# EquisatSimulatorV2.net
KiCad netlist of a schematic drawn in EAGLE
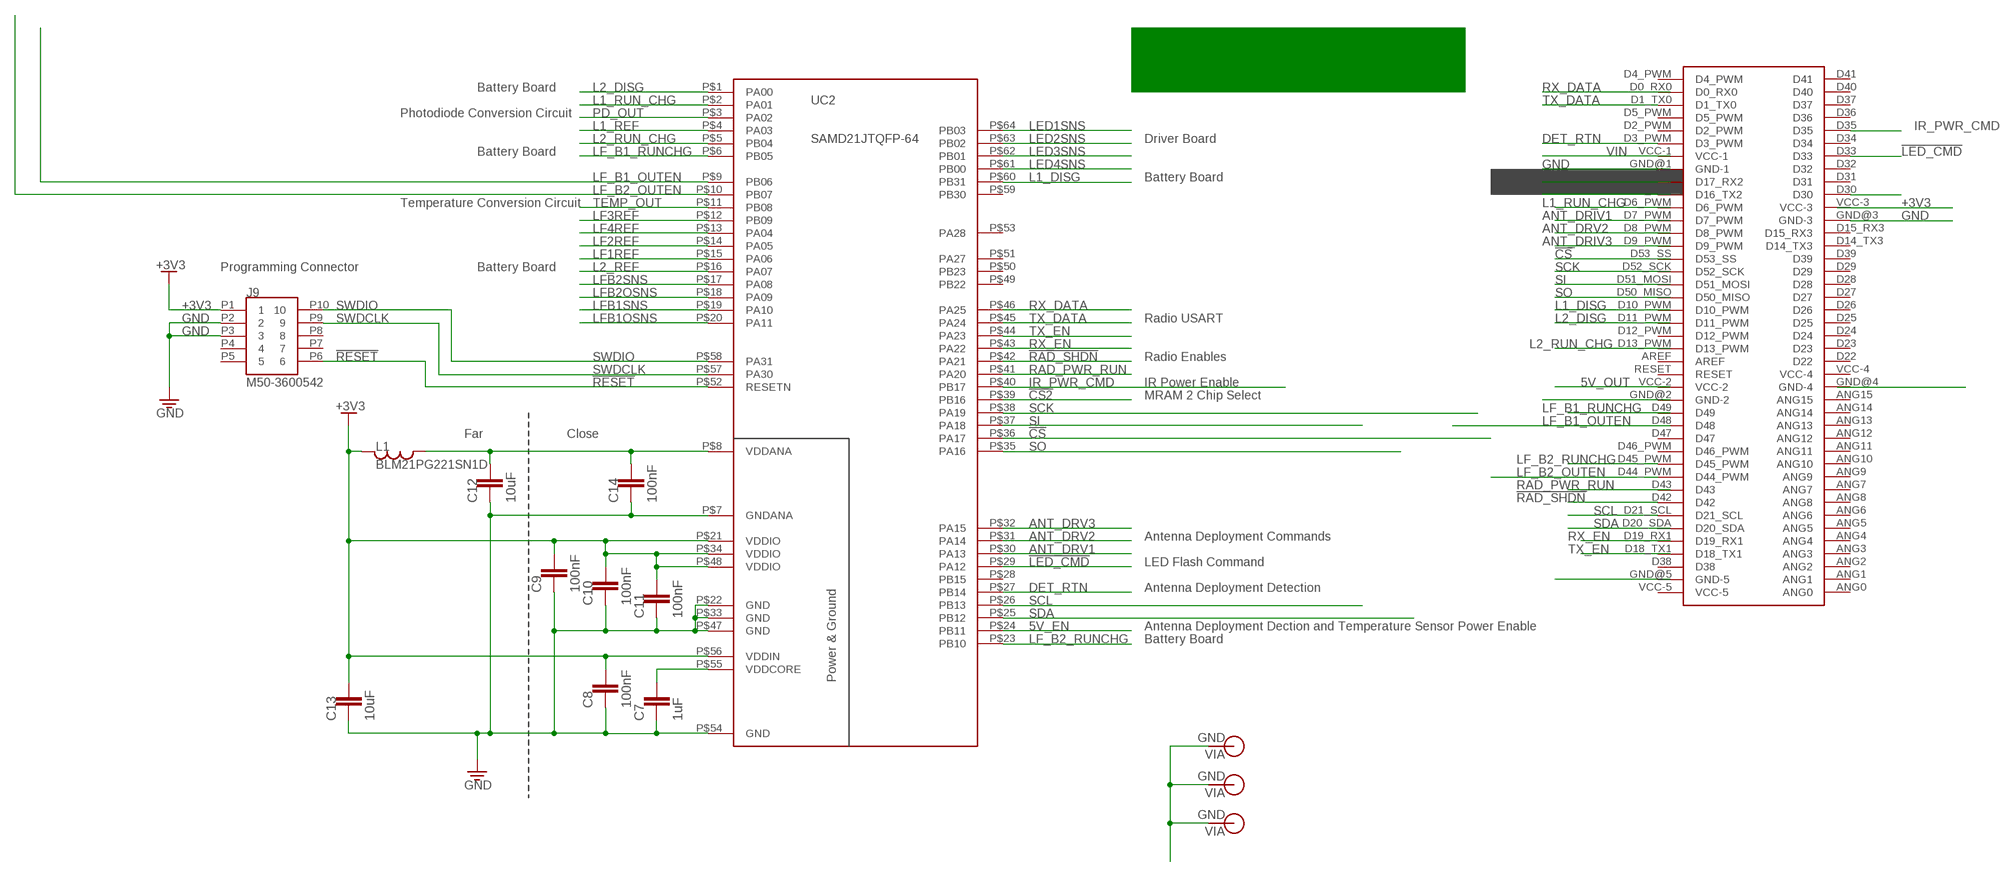
[diagram p0: schematic, sheet 1]

(export (version "E")
  (design (tool "Eeschema 10.0.6"))
  (components
    (comp (ref "C7")
      (value "1uF")
      (footprint "eagle-import:0805")
      (libsource (lib "eagle-import") (part "CAP0805"))
    )
    (comp (ref "C8")
      (value "100nF")
      (footprint "eagle-import:0805")
      (libsource (lib "eagle-import") (part "CAP0805"))
    )
    (comp (ref "C9")
      (value "100nF")
      (footprint "eagle-import:0805")
      (libsource (lib "eagle-import") (part "CAP0805"))
    )
    (comp (ref "C10")
      (value "100nF")
      (footprint "eagle-import:0805")
      (libsource (lib "eagle-import") (part "CAP0805"))
    )
    (comp (ref "C11")
      (value "100nF")
      (footprint "eagle-import:0805")
      (libsource (lib "eagle-import") (part "CAP0805"))
    )
    (comp (ref "C12")
      (value "10uF")
      (footprint "eagle-import:0805")
      (libsource (lib "eagle-import") (part "CAP0805"))
    )
    (comp (ref "C13")
      (value "10uF")
      (footprint "eagle-import:0805")
      (libsource (lib "eagle-import") (part "CAP0805"))
    )
    (comp (ref "C14")
      (value "100nF")
      (footprint "eagle-import:0805")
      (libsource (lib "eagle-import") (part "CAP0805"))
    )
    (comp (ref "J9")
      (value "M50-3600542")
      (footprint "eagle-import:10PINMALE")
      (libsource (lib "eagle-import") (part "10PINMALE"))
    )
    (comp (ref "L1")
      (value "BLM21PG221SN1D")
      (footprint "eagle-import:0805")
      (libsource (lib "eagle-import") (part "FERRITE"))
    )
    (comp (ref "U$1")
      (value "ARDUINOMEGABOARD")
      (footprint "eagle-import:ARDUINOMEGA")
      (libsource (lib "eagle-import") (part "ARDUINOMEGABOARD"))
    )
    (comp (ref "UC2")
      (value "SAMD21JTQFP-64")
      (footprint "eagle-import:TQFP-64")
      (libsource (lib "eagle-import") (part "SAMD21JTQFP-64"))
    )
    (comp (ref "V9")
      (value "GND")
      (footprint "eagle-import:VIA-60MIL-SQ")
      (libsource (lib "eagle-import") (part "VIA60MIL-SQ"))
    )
    (comp (ref "V10")
      (value "GND")
      (footprint "eagle-import:VIA-60MIL-SQ")
      (libsource (lib "eagle-import") (part "VIA60MIL-SQ"))
    )
    (comp (ref "V12")
      (value "GND")
      (footprint "eagle-import:VIA-60MIL-SQ")
      (libsource (lib "eagle-import") (part "VIA60MIL-SQ"))
    )
  )
  (nets
    (net (code "1") (name "+3V3") (class "Default")
      (node (ref "C10") (pin "1") (pinfunction "P$1_1") (pintype "passive"))
      (node (ref "C11") (pin "1") (pinfunction "P$1_1") (pintype "passive"))
      (node (ref "C13") (pin "1") (pinfunction "P$1_1") (pintype "passive"))
      (node (ref "C8") (pin "1") (pinfunction "P$1_1") (pintype "passive"))
      (node (ref "C9") (pin "1") (pinfunction "P$1_1") (pintype "passive"))
      (node (ref "J9") (pin "P1") (pinfunction "1_P1") (pintype "bidirectional"))
      (node (ref "L1") (pin "1") (pinfunction "P$1_1") (pintype "passive"))
      (node (ref "UC2") (pin "P$21") (pinfunction "VDDIO_P$21") (pintype "power_in"))
      (node (ref "UC2") (pin "P$34") (pinfunction "VDDIO_P$34") (pintype "power_in"))
      (node (ref "UC2") (pin "P$48") (pinfunction "VDDIO_P$48") (pintype "power_in"))
      (node (ref "UC2") (pin "P$56") (pinfunction "VDDIN_P$56") (pintype "power_in"))
    )
    (net (code "2") (name "5V_EN") (class "Default")
      (node (ref "UC2") (pin "P$24") (pinfunction "PB11_P$24") (pintype "bidirectional"))
    )
    (net (code "6") (name "ANT_DRV1") (class "Default")
      (node (ref "UC2") (pin "P$30") (pinfunction "PA13_P$30") (pintype "bidirectional"))
    )
    (net (code "7") (name "ANT_DRV2") (class "Default")
      (node (ref "UC2") (pin "P$31") (pinfunction "PA14_P$31") (pintype "bidirectional"))
    )
    (net (code "8") (name "ANT_DRV3") (class "Default")
      (node (ref "UC2") (pin "P$32") (pinfunction "PA15_P$32") (pintype "bidirectional"))
    )
    (net (code "9") (name "DET_RTN") (class "Default")
      (node (ref "U$1") (pin "D3_PWM") (pinfunction "D3_PWM_D3_PWM") (pintype "bidirectional"))
      (node (ref "UC2") (pin "P$27") (pinfunction "PB14_P$27") (pintype "bidirectional"))
    )
    (net (code "10") (name "GND") (class "Default")
      (node (ref "C10") (pin "2") (pinfunction "P$2_2") (pintype "passive"))
      (node (ref "C11") (pin "2") (pinfunction "P$2_2") (pintype "passive"))
      (node (ref "C12") (pin "2") (pinfunction "P$2_2") (pintype "passive"))
      (node (ref "C13") (pin "2") (pinfunction "P$2_2") (pintype "passive"))
      (node (ref "C14") (pin "2") (pinfunction "P$2_2") (pintype "passive"))
      (node (ref "C7") (pin "2") (pinfunction "P$2_2") (pintype "passive"))
      (node (ref "C8") (pin "2") (pinfunction "P$2_2") (pintype "passive"))
      (node (ref "C9") (pin "2") (pinfunction "P$2_2") (pintype "passive"))
      (node (ref "J9") (pin "P2") (pinfunction "2_P2") (pintype "bidirectional"))
      (node (ref "J9") (pin "P3") (pinfunction "3_P3") (pintype "bidirectional"))
      (node (ref "U$1") (pin "GND@3") (pinfunction "GND-3_GND@3") (pintype "bidirectional"))
      (node (ref "UC2") (pin "P$22") (pinfunction "GND_P$22") (pintype "power_in"))
      (node (ref "UC2") (pin "P$33") (pinfunction "GND_P$33") (pintype "power_in"))
      (node (ref "UC2") (pin "P$47") (pinfunction "GND_P$47") (pintype "power_in"))
      (node (ref "UC2") (pin "P$54") (pinfunction "GND_P$54") (pintype "power_in"))
      (node (ref "UC2") (pin "P$7") (pinfunction "GNDANA_P$7") (pintype "power_in"))
      (node (ref "V10") (pin "P$1") (pinfunction "P$1_P$1") (pintype "bidirectional"))
      (node (ref "V12") (pin "P$1") (pinfunction "P$1_P$1") (pintype "bidirectional"))
      (node (ref "V9") (pin "P$1") (pinfunction "P$1_P$1") (pintype "bidirectional"))
    )
    (net (code "11") (name "IR_PWR_CMD") (class "Default")
      (node (ref "U$1") (pin "D35") (pinfunction "D35_D35") (pintype "bidirectional"))
      (node (ref "UC2") (pin "P$40") (pinfunction "PB17_P$40") (pintype "bidirectional"))
    )
    (net (code "12") (name "L1_DISG") (class "Default")
      (node (ref "UC2") (pin "P$60") (pinfunction "PB31_P$60") (pintype "bidirectional"))
    )
    (net (code "13") (name "L1_REF") (class "Default")
      (node (ref "UC2") (pin "P$4") (pinfunction "PA03_P$4") (pintype "bidirectional"))
    )
    (net (code "14") (name "L1_RUN_CHG") (class "Default")
      (node (ref "UC2") (pin "P$2") (pinfunction "PA01_P$2") (pintype "bidirectional"))
    )
    (net (code "15") (name "L2_DISG") (class "Default")
      (node (ref "UC2") (pin "P$1") (pinfunction "PA00_P$1") (pintype "bidirectional"))
    )
    (net (code "16") (name "L2_REF") (class "Default")
      (node (ref "UC2") (pin "P$16") (pinfunction "PA07_P$16") (pintype "bidirectional"))
    )
    (net (code "17") (name "L2_RUN_CHG") (class "Default")
      (node (ref "UC2") (pin "P$5") (pinfunction "PB04_P$5") (pintype "bidirectional"))
    )
    (net (code "18") (name "LED1SNS") (class "Default")
      (node (ref "UC2") (pin "P$64") (pinfunction "PB03_P$64") (pintype "bidirectional"))
    )
    (net (code "19") (name "LED2SNS") (class "Default")
      (node (ref "UC2") (pin "P$63") (pinfunction "PB02_P$63") (pintype "bidirectional"))
    )
    (net (code "20") (name "LED3SNS") (class "Default")
      (node (ref "UC2") (pin "P$62") (pinfunction "PB01_P$62") (pintype "bidirectional"))
    )
    (net (code "21") (name "LED4SNS") (class "Default")
      (node (ref "UC2") (pin "P$61") (pinfunction "PB00_P$61") (pintype "bidirectional"))
    )
    (net (code "22") (name "LF1REF") (class "Default")
      (node (ref "UC2") (pin "P$15") (pinfunction "PA06_P$15") (pintype "bidirectional"))
    )
    (net (code "23") (name "LF2REF") (class "Default")
      (node (ref "UC2") (pin "P$14") (pinfunction "PA05_P$14") (pintype "bidirectional"))
    )
    (net (code "24") (name "LF3REF") (class "Default")
      (node (ref "UC2") (pin "P$12") (pinfunction "PB09_P$12") (pintype "bidirectional"))
    )
    (net (code "25") (name "LF4REF") (class "Default")
      (node (ref "UC2") (pin "P$13") (pinfunction "PA04_P$13") (pintype "bidirectional"))
    )
    (net (code "26") (name "LFB1OSNS") (class "Default")
      (node (ref "UC2") (pin "P$20") (pinfunction "PA11_P$20") (pintype "bidirectional"))
    )
    (net (code "27") (name "LFB1SNS") (class "Default")
      (node (ref "UC2") (pin "P$19") (pinfunction "PA10_P$19") (pintype "bidirectional"))
    )
    (net (code "28") (name "LFB2OSNS") (class "Default")
      (node (ref "UC2") (pin "P$18") (pinfunction "PA09_P$18") (pintype "bidirectional"))
    )
    (net (code "29") (name "LFB2SNS") (class "Default")
      (node (ref "UC2") (pin "P$17") (pinfunction "PA08_P$17") (pintype "bidirectional"))
    )
    (net (code "30") (name "LF_B1_OUTEN") (class "Default")
      (node (ref "UC2") (pin "P$9") (pinfunction "PB06_P$9") (pintype "bidirectional"))
    )
    (net (code "31") (name "LF_B1_RUNCHG") (class "Default")
      (node (ref "UC2") (pin "P$6") (pinfunction "PB05_P$6") (pintype "bidirectional"))
    )
    (net (code "32") (name "LF_B2_OUTEN") (class "Default")
      (node (ref "U$1") (pin "D44_PWM") (pinfunction "D44_PWM_D44_PWM") (pintype "bidirectional"))
      (node (ref "UC2") (pin "P$10") (pinfunction "PB07_P$10") (pintype "bidirectional"))
    )
    (net (code "33") (name "LF_B2_RUNCHG") (class "Default")
      (node (ref "U$1") (pin "D45_PWM") (pinfunction "D45_PWM_D45_PWM") (pintype "bidirectional"))
      (node (ref "UC2") (pin "P$23") (pinfunction "PB10_P$23") (pintype "bidirectional"))
    )
    (net (code "34") (name "Net-(C7-P$1)") (class "Default")
      (node (ref "C7") (pin "1") (pinfunction "P$1_1") (pintype "passive"))
      (node (ref "UC2") (pin "P$55") (pinfunction "VDDCORE_P$55") (pintype "power_in"))
    )
    (net (code "35") (name "Net-(C12-P$1)") (class "Default")
      (node (ref "C12") (pin "1") (pinfunction "P$1_1") (pintype "passive"))
      (node (ref "C14") (pin "1") (pinfunction "P$1_1") (pintype "passive"))
      (node (ref "L1") (pin "2") (pinfunction "P$2_2") (pintype "passive"))
      (node (ref "UC2") (pin "P$8") (pinfunction "VDDANA_P$8") (pintype "power_in"))
    )
    (net (code "36") (name "PD_OUT") (class "Default")
      (node (ref "UC2") (pin "P$3") (pinfunction "PA02_P$3") (pintype "bidirectional"))
    )
    (net (code "37") (name "RAD_PWR_RUN") (class "Default")
      (node (ref "UC2") (pin "P$41") (pinfunction "PA20_P$41") (pintype "bidirectional"))
    )
    (net (code "39") (name "RX_DATA") (class "Default")
      (node (ref "UC2") (pin "P$46") (pinfunction "PA25_P$46") (pintype "bidirectional"))
    )
    (net (code "40") (name "RX_EN") (class "Default")
      (node (ref "UC2") (pin "P$43") (pinfunction "PA22_P$43") (pintype "bidirectional"))
    )
    (net (code "41") (name "SCK") (class "Default")
      (node (ref "UC2") (pin "P$38") (pinfunction "PA19_P$38") (pintype "bidirectional"))
    )
    (net (code "42") (name "SCL") (class "Default")
      (node (ref "U$1") (pin "D21_SCL") (pinfunction "D21_SCL_D21_SCL") (pintype "bidirectional"))
      (node (ref "UC2") (pin "P$26") (pinfunction "PB13_P$26") (pintype "bidirectional"))
    )
    (net (code "43") (name "SDA") (class "Default")
      (node (ref "UC2") (pin "P$25") (pinfunction "PB12_P$25") (pintype "bidirectional"))
    )
    (net (code "44") (name "SI") (class "Default")
      (node (ref "UC2") (pin "P$37") (pinfunction "PA18_P$37") (pintype "bidirectional"))
    )
    (net (code "45") (name "SO") (class "Default")
      (node (ref "UC2") (pin "P$35") (pinfunction "PA16_P$35") (pintype "bidirectional"))
    )
    (net (code "46") (name "SWDCLK") (class "Default")
      (node (ref "J9") (pin "P9") (pinfunction "9_P9") (pintype "bidirectional"))
      (node (ref "UC2") (pin "P$57") (pinfunction "PA30_P$57") (pintype "bidirectional"))
    )
    (net (code "47") (name "SWDIO") (class "Default")
      (node (ref "J9") (pin "P10") (pinfunction "10_P10") (pintype "bidirectional"))
      (node (ref "UC2") (pin "P$58") (pinfunction "PA31_P$58") (pintype "bidirectional"))
    )
    (net (code "48") (name "TEMP_OUT") (class "Default")
      (node (ref "UC2") (pin "P$11") (pinfunction "PB08_P$11") (pintype "bidirectional"))
    )
    (net (code "50") (name "TX_DATA") (class "Default")
      (node (ref "U$1") (pin "D1_TX0") (pinfunction "D1_TX0_D1_TX0") (pintype "bidirectional"))
      (node (ref "UC2") (pin "P$45") (pinfunction "PA24_P$45") (pintype "bidirectional"))
    )
    (net (code "51") (name "TX_EN") (class "Default")
      (node (ref "UC2") (pin "P$44") (pinfunction "PA23_P$44") (pintype "bidirectional"))
    )
    (net (code "53") (name "unconnected-(J9-4-PadP4)") (class "Default")
      (node (ref "J9") (pin "P4") (pinfunction "4_P4") (pintype "bidirectional"))
    )
    (net (code "54") (name "unconnected-(J9-5-PadP5)") (class "Default")
      (node (ref "J9") (pin "P5") (pinfunction "5_P5") (pintype "bidirectional"))
    )
    (net (code "55") (name "unconnected-(J9-7-PadP7)") (class "Default")
      (node (ref "J9") (pin "P7") (pinfunction "7_P7") (pintype "bidirectional"))
    )
    (net (code "56") (name "unconnected-(J9-8-PadP8)") (class "Default")
      (node (ref "J9") (pin "P8") (pinfunction "8_P8") (pintype "bidirectional"))
    )
    (net (code "57") (name "unconnected-(U$1-GND-1-PadGND@1)") (class "Default")
      (node (ref "U$1") (pin "GND@1") (pinfunction "GND-1_GND@1") (pintype "bidirectional"))
    )
    (net (code "58") (name "unconnected-(U$1-GND-2-PadGND@2)") (class "Default")
      (node (ref "U$1") (pin "GND@2") (pinfunction "GND-2_GND@2") (pintype "bidirectional"))
    )
    (net (code "59") (name "unconnected-(U$1-GND-4-PadGND@4)") (class "Default")
      (node (ref "U$1") (pin "GND@4") (pinfunction "GND-4_GND@4") (pintype "bidirectional"))
    )
    (net (code "60") (name "unconnected-(U$1-GND-5-PadGND@5)") (class "Default")
      (node (ref "U$1") (pin "GND@5") (pinfunction "GND-5_GND@5") (pintype "bidirectional"))
    )
    (net (code "61") (name "unconnected-(U$1-PadANG0)") (class "Default")
      (node (ref "U$1") (pin "ANG0") (pinfunction "ANG0_ANG0") (pintype "bidirectional"))
    )
    (net (code "62") (name "unconnected-(U$1-PadANG1)") (class "Default")
      (node (ref "U$1") (pin "ANG1") (pinfunction "ANG1_ANG1") (pintype "bidirectional"))
    )
    (net (code "63") (name "unconnected-(U$1-PadANG2)") (class "Default")
      (node (ref "U$1") (pin "ANG2") (pinfunction "ANG2_ANG2") (pintype "bidirectional"))
    )
    (net (code "64") (name "unconnected-(U$1-PadANG3)") (class "Default")
      (node (ref "U$1") (pin "ANG3") (pinfunction "ANG3_ANG3") (pintype "bidirectional"))
    )
    (net (code "65") (name "unconnected-(U$1-PadANG4)") (class "Default")
      (node (ref "U$1") (pin "ANG4") (pinfunction "ANG4_ANG4") (pintype "bidirectional"))
    )
    (net (code "66") (name "unconnected-(U$1-PadANG5)") (class "Default")
      (node (ref "U$1") (pin "ANG5") (pinfunction "ANG5_ANG5") (pintype "bidirectional"))
    )
    (net (code "67") (name "unconnected-(U$1-PadANG6)") (class "Default")
      (node (ref "U$1") (pin "ANG6") (pinfunction "ANG6_ANG6") (pintype "bidirectional"))
    )
    (net (code "68") (name "unconnected-(U$1-PadANG7)") (class "Default")
      (node (ref "U$1") (pin "ANG7") (pinfunction "ANG7_ANG7") (pintype "bidirectional"))
    )
    (net (code "69") (name "unconnected-(U$1-PadANG8)") (class "Default")
      (node (ref "U$1") (pin "ANG8") (pinfunction "ANG8_ANG8") (pintype "bidirectional"))
    )
    (net (code "70") (name "unconnected-(U$1-PadANG9)") (class "Default")
      (node (ref "U$1") (pin "ANG9") (pinfunction "ANG9_ANG9") (pintype "bidirectional"))
    )
    (net (code "71") (name "unconnected-(U$1-PadANG10)") (class "Default")
      (node (ref "U$1") (pin "ANG10") (pinfunction "ANG10_ANG10") (pintype "bidirectional"))
    )
    (net (code "72") (name "unconnected-(U$1-PadANG11)") (class "Default")
      (node (ref "U$1") (pin "ANG11") (pinfunction "ANG11_ANG11") (pintype "bidirectional"))
    )
    (net (code "73") (name "unconnected-(U$1-PadANG12)") (class "Default")
      (node (ref "U$1") (pin "ANG12") (pinfunction "ANG12_ANG12") (pintype "bidirectional"))
    )
    (net (code "74") (name "unconnected-(U$1-PadANG13)") (class "Default")
      (node (ref "U$1") (pin "ANG13") (pinfunction "ANG13_ANG13") (pintype "bidirectional"))
    )
    (net (code "75") (name "unconnected-(U$1-PadANG14)") (class "Default")
      (node (ref "U$1") (pin "ANG14") (pinfunction "ANG14_ANG14") (pintype "bidirectional"))
    )
    (net (code "76") (name "unconnected-(U$1-PadANG15)") (class "Default")
      (node (ref "U$1") (pin "ANG15") (pinfunction "ANG15_ANG15") (pintype "bidirectional"))
    )
    (net (code "77") (name "unconnected-(U$1-PadAREF)") (class "Default")
      (node (ref "U$1") (pin "AREF") (pinfunction "AREF_AREF") (pintype "bidirectional"))
    )
    (net (code "78") (name "unconnected-(U$1-PadD0_RX0)") (class "Default")
      (node (ref "U$1") (pin "D0_RX0") (pinfunction "D0_RX0_D0_RX0") (pintype "bidirectional"))
    )
    (net (code "79") (name "unconnected-(U$1-PadD2_PWM)") (class "Default")
      (node (ref "U$1") (pin "D2_PWM") (pinfunction "D2_PWM_D2_PWM") (pintype "bidirectional"))
    )
    (net (code "80") (name "unconnected-(U$1-PadD4_PWM)") (class "Default")
      (node (ref "U$1") (pin "D4_PWM") (pinfunction "D4_PWM_D4_PWM") (pintype "bidirectional"))
    )
    (net (code "81") (name "unconnected-(U$1-PadD5_PWM)") (class "Default")
      (node (ref "U$1") (pin "D5_PWM") (pinfunction "D5_PWM_D5_PWM") (pintype "bidirectional"))
    )
    (net (code "82") (name "unconnected-(U$1-PadD6_PWM)") (class "Default")
      (node (ref "U$1") (pin "D6_PWM") (pinfunction "D6_PWM_D6_PWM") (pintype "bidirectional"))
    )
    (net (code "83") (name "unconnected-(U$1-PadD7_PWM)") (class "Default")
      (node (ref "U$1") (pin "D7_PWM") (pinfunction "D7_PWM_D7_PWM") (pintype "bidirectional"))
    )
    (net (code "84") (name "unconnected-(U$1-PadD8_PWM)") (class "Default")
      (node (ref "U$1") (pin "D8_PWM") (pinfunction "D8_PWM_D8_PWM") (pintype "bidirectional"))
    )
    (net (code "85") (name "unconnected-(U$1-PadD9_PWM)") (class "Default")
      (node (ref "U$1") (pin "D9_PWM") (pinfunction "D9_PWM_D9_PWM") (pintype "bidirectional"))
    )
    (net (code "86") (name "unconnected-(U$1-PadD10_PWM)") (class "Default")
      (node (ref "U$1") (pin "D10_PWM") (pinfunction "D10_PWM_D10_PWM") (pintype "bidirectional"))
    )
    (net (code "87") (name "unconnected-(U$1-PadD11_PWM)") (class "Default")
      (node (ref "U$1") (pin "D11_PWM") (pinfunction "D11_PWM_D11_PWM") (pintype "bidirectional"))
    )
    (net (code "88") (name "unconnected-(U$1-PadD12_PWM)") (class "Default")
      (node (ref "U$1") (pin "D12_PWM") (pinfunction "D12_PWM_D12_PWM") (pintype "bidirectional"))
    )
    (net (code "89") (name "unconnected-(U$1-PadD13_PWM)") (class "Default")
      (node (ref "U$1") (pin "D13_PWM") (pinfunction "D13_PWM_D13_PWM") (pintype "bidirectional"))
    )
    (net (code "90") (name "unconnected-(U$1-PadD14_TX3)") (class "Default")
      (node (ref "U$1") (pin "D14_TX3") (pinfunction "D14_TX3_D14_TX3") (pintype "bidirectional"))
    )
    (net (code "91") (name "unconnected-(U$1-PadD15_RX3)") (class "Default")
      (node (ref "U$1") (pin "D15_RX3") (pinfunction "D15_RX3_D15_RX3") (pintype "bidirectional"))
    )
    (net (code "92") (name "unconnected-(U$1-PadD16_TX2)") (class "Default")
      (node (ref "U$1") (pin "D16_TX2") (pinfunction "D16_TX2_D16_TX2") (pintype "bidirectional"))
    )
    (net (code "93") (name "unconnected-(U$1-PadD17_RX2)") (class "Default")
      (node (ref "U$1") (pin "D17_RX2") (pinfunction "D17_RX2_D17_RX2") (pintype "bidirectional"))
    )
    (net (code "94") (name "unconnected-(U$1-PadD18_TX1)") (class "Default")
      (node (ref "U$1") (pin "D18_TX1") (pinfunction "D18_TX1_D18_TX1") (pintype "bidirectional"))
    )
    (net (code "95") (name "unconnected-(U$1-PadD19_RX1)") (class "Default")
      (node (ref "U$1") (pin "D19_RX1") (pinfunction "D19_RX1_D19_RX1") (pintype "bidirectional"))
    )
    (net (code "96") (name "unconnected-(U$1-PadD20_SDA)") (class "Default")
      (node (ref "U$1") (pin "D20_SDA") (pinfunction "D20_SDA_D20_SDA") (pintype "bidirectional"))
    )
    (net (code "97") (name "unconnected-(U$1-PadD22)") (class "Default")
      (node (ref "U$1") (pin "D22") (pinfunction "D22_D22") (pintype "bidirectional"))
    )
    (net (code "98") (name "unconnected-(U$1-PadD23)") (class "Default")
      (node (ref "U$1") (pin "D23") (pinfunction "D23_D23") (pintype "bidirectional"))
    )
    (net (code "99") (name "unconnected-(U$1-PadD24)") (class "Default")
      (node (ref "U$1") (pin "D24") (pinfunction "D24_D24") (pintype "bidirectional"))
    )
    (net (code "100") (name "unconnected-(U$1-PadD25)") (class "Default")
      (node (ref "U$1") (pin "D25") (pinfunction "D25_D25") (pintype "bidirectional"))
    )
    (net (code "101") (name "unconnected-(U$1-PadD26)") (class "Default")
      (node (ref "U$1") (pin "D26") (pinfunction "D26_D26") (pintype "bidirectional"))
    )
    (net (code "102") (name "unconnected-(U$1-PadD27)") (class "Default")
      (node (ref "U$1") (pin "D27") (pinfunction "D27_D27") (pintype "bidirectional"))
    )
    (net (code "103") (name "unconnected-(U$1-PadD28)") (class "Default")
      (node (ref "U$1") (pin "D28") (pinfunction "D28_D28") (pintype "bidirectional"))
    )
    (net (code "104") (name "unconnected-(U$1-PadD29)") (class "Default")
      (node (ref "U$1") (pin "D29") (pinfunction "D29_D29") (pintype "bidirectional"))
    )
    (net (code "105") (name "unconnected-(U$1-PadD30)") (class "Default")
      (node (ref "U$1") (pin "D30") (pinfunction "D30_D30") (pintype "bidirectional"))
    )
    (net (code "106") (name "unconnected-(U$1-PadD31)") (class "Default")
      (node (ref "U$1") (pin "D31") (pinfunction "D31_D31") (pintype "bidirectional"))
    )
    (net (code "107") (name "unconnected-(U$1-PadD32)") (class "Default")
      (node (ref "U$1") (pin "D32") (pinfunction "D32_D32") (pintype "bidirectional"))
    )
    (net (code "108") (name "unconnected-(U$1-PadD34)") (class "Default")
      (node (ref "U$1") (pin "D34") (pinfunction "D34_D34") (pintype "bidirectional"))
    )
    (net (code "109") (name "unconnected-(U$1-PadD36)") (class "Default")
      (node (ref "U$1") (pin "D36") (pinfunction "D36_D36") (pintype "bidirectional"))
    )
    (net (code "110") (name "unconnected-(U$1-PadD37)") (class "Default")
      (node (ref "U$1") (pin "D37") (pinfunction "D37_D37") (pintype "bidirectional"))
    )
    (net (code "111") (name "unconnected-(U$1-PadD38)") (class "Default")
      (node (ref "U$1") (pin "D38") (pinfunction "D38_D38") (pintype "bidirectional"))
    )
    (net (code "112") (name "unconnected-(U$1-PadD39)") (class "Default")
      (node (ref "U$1") (pin "D39") (pinfunction "D39_D39") (pintype "bidirectional"))
    )
    (net (code "113") (name "unconnected-(U$1-PadD40)") (class "Default")
      (node (ref "U$1") (pin "D40") (pinfunction "D40_D40") (pintype "bidirectional"))
    )
    (net (code "114") (name "unconnected-(U$1-PadD41)") (class "Default")
      (node (ref "U$1") (pin "D41") (pinfunction "D41_D41") (pintype "bidirectional"))
    )
    (net (code "115") (name "unconnected-(U$1-PadD43)") (class "Default")
      (node (ref "U$1") (pin "D43") (pinfunction "D43_D43") (pintype "bidirectional"))
    )
    (net (code "116") (name "unconnected-(U$1-PadD46_PWM)") (class "Default")
      (node (ref "U$1") (pin "D46_PWM") (pinfunction "D46_PWM_D46_PWM") (pintype "bidirectional"))
    )
    (net (code "117") (name "unconnected-(U$1-PadD47)") (class "Default")
      (node (ref "U$1") (pin "D47") (pinfunction "D47_D47") (pintype "bidirectional"))
    )
    (net (code "118") (name "unconnected-(U$1-PadD48)") (class "Default")
      (node (ref "U$1") (pin "D48") (pinfunction "D48_D48") (pintype "bidirectional"))
    )
    (net (code "119") (name "unconnected-(U$1-PadD49)") (class "Default")
      (node (ref "U$1") (pin "D49") (pinfunction "D49_D49") (pintype "bidirectional"))
    )
    (net (code "120") (name "unconnected-(U$1-PadD50_MISO)") (class "Default")
      (node (ref "U$1") (pin "D50_MISO") (pinfunction "D50_MISO_D50_MISO") (pintype "bidirectional"))
    )
    (net (code "121") (name "unconnected-(U$1-PadD51_MOSI)") (class "Default")
      (node (ref "U$1") (pin "D51_MOSI") (pinfunction "D51_MOSI_D51_MOSI") (pintype "bidirectional"))
    )
    (net (code "122") (name "unconnected-(U$1-PadD52_SCK)") (class "Default")
      (node (ref "U$1") (pin "D52_SCK") (pinfunction "D52_SCK_D52_SCK") (pintype "bidirectional"))
    )
    (net (code "123") (name "unconnected-(U$1-PadD53_SS)") (class "Default")
      (node (ref "U$1") (pin "D53_SS") (pinfunction "D53_SS_D53_SS") (pintype "bidirectional"))
    )
    (net (code "124") (name "unconnected-(U$1-PadRESET)") (class "Default")
      (node (ref "U$1") (pin "RESET") (pinfunction "RESET_RESET") (pintype "bidirectional"))
    )
    (net (code "125") (name "unconnected-(U$1-PadVCC-1)") (class "Default")
      (node (ref "U$1") (pin "VCC-1") (pinfunction "VCC-1_VCC-1") (pintype "bidirectional"))
    )
    (net (code "126") (name "unconnected-(U$1-PadVCC-2)") (class "Default")
      (node (ref "U$1") (pin "VCC-2") (pinfunction "VCC-2_VCC-2") (pintype "bidirectional"))
    )
    (net (code "127") (name "unconnected-(U$1-PadVCC-3)") (class "Default")
      (node (ref "U$1") (pin "VCC-3") (pinfunction "VCC-3_VCC-3") (pintype "bidirectional"))
    )
    (net (code "128") (name "unconnected-(U$1-PadVCC-4)") (class "Default")
      (node (ref "U$1") (pin "VCC-4") (pinfunction "VCC-4_VCC-4") (pintype "bidirectional"))
    )
    (net (code "129") (name "unconnected-(U$1-PadVCC-5)") (class "Default")
      (node (ref "U$1") (pin "VCC-5") (pinfunction "VCC-5_VCC-5") (pintype "bidirectional"))
    )
    (net (code "130") (name "unconnected-(UC2-PA27-PadP$51)") (class "Default")
      (node (ref "UC2") (pin "P$51") (pinfunction "PA27_P$51") (pintype "bidirectional"))
    )
    (net (code "131") (name "unconnected-(UC2-PA28-PadP$53)") (class "Default")
      (node (ref "UC2") (pin "P$53") (pinfunction "PA28_P$53") (pintype "bidirectional"))
    )
    (net (code "132") (name "unconnected-(UC2-PB15-PadP$28)") (class "Default")
      (node (ref "UC2") (pin "P$28") (pinfunction "PB15_P$28") (pintype "bidirectional"))
    )
    (net (code "133") (name "unconnected-(UC2-PB22-PadP$49)") (class "Default")
      (node (ref "UC2") (pin "P$49") (pinfunction "PB22_P$49") (pintype "bidirectional"))
    )
    (net (code "134") (name "unconnected-(UC2-PB23-PadP$50)") (class "Default")
      (node (ref "UC2") (pin "P$50") (pinfunction "PB23_P$50") (pintype "bidirectional"))
    )
    (net (code "135") (name "unconnected-(UC2-PB30-PadP$59)") (class "Default")
      (node (ref "UC2") (pin "P$59") (pinfunction "PB30_P$59") (pintype "bidirectional"))
    )
    (net (code "136") (name "~{CS2}") (class "Default")
      (node (ref "UC2") (pin "P$39") (pinfunction "PB16_P$39") (pintype "bidirectional"))
    )
    (net (code "137") (name "~{CS}") (class "Default")
      (node (ref "UC2") (pin "P$36") (pinfunction "PA17_P$36") (pintype "bidirectional"))
    )
    (net (code "138") (name "~{LED_CMD}") (class "Default")
      (node (ref "U$1") (pin "D33") (pinfunction "D33_D33") (pintype "bidirectional"))
      (node (ref "UC2") (pin "P$29") (pinfunction "PA12_P$29") (pintype "bidirectional"))
    )
    (net (code "139") (name "~{RAD_SHDN}") (class "Default")
      (node (ref "U$1") (pin "D42") (pinfunction "D42_D42") (pintype "bidirectional"))
      (node (ref "UC2") (pin "P$42") (pinfunction "PA21_P$42") (pintype "bidirectional"))
    )
    (net (code "140") (name "~{RESET}") (class "Default")
      (node (ref "J9") (pin "P6") (pinfunction "6_P6") (pintype "bidirectional"))
      (node (ref "UC2") (pin "P$52") (pinfunction "RESETN_P$52") (pintype "input"))
    )
  )
)
